# Fostex_CTRL.net
KiCad netlist of a schematic drawn in EAGLE
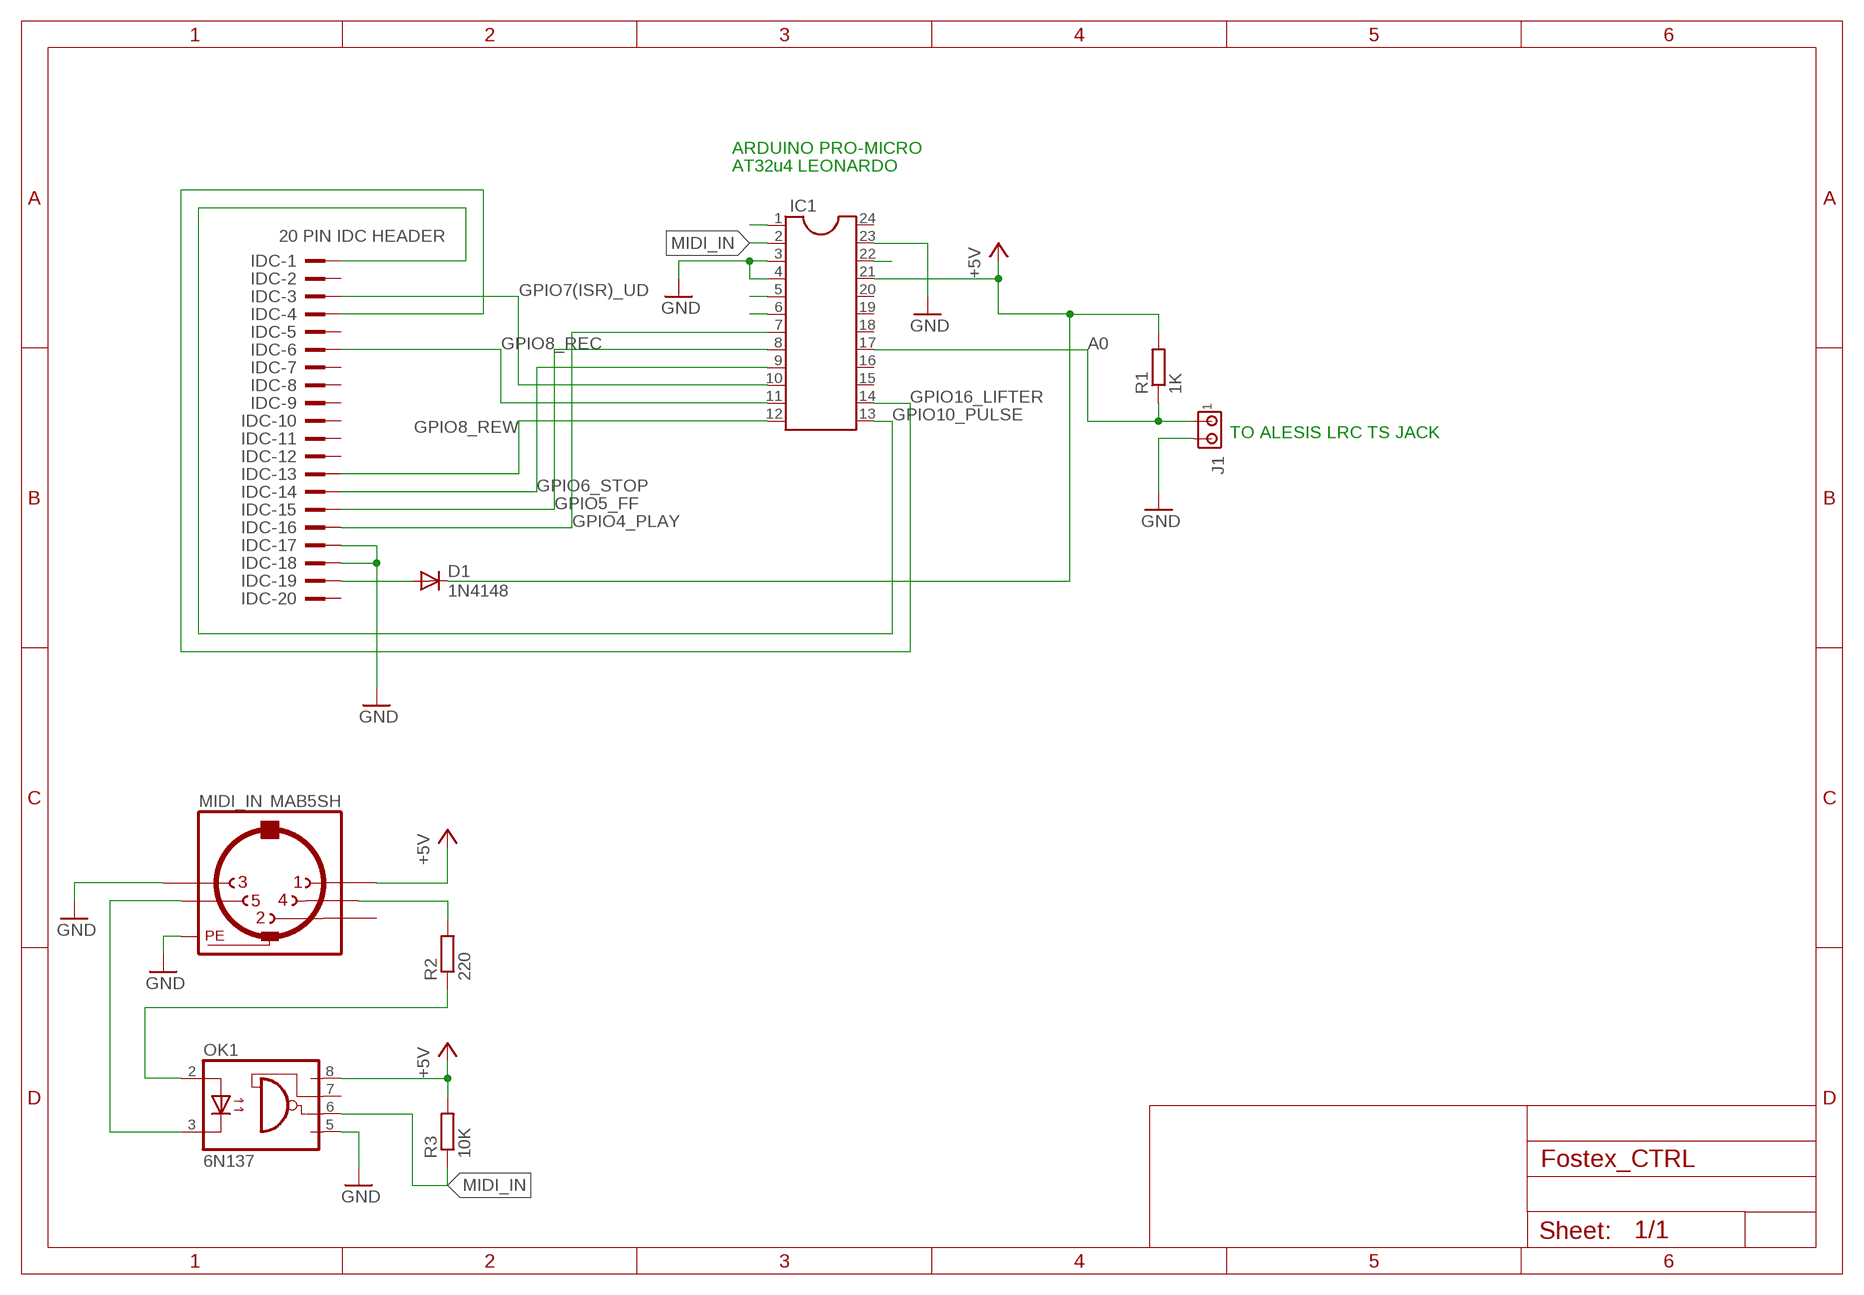
[diagram p0: schematic, sheet 1]

(export (version "E")
  (design (tool "Eeschema 10.0.6"))
  (components
    (comp (ref "D1")
      (value "1N4148")
      (footprint "eagle-import:DO35-7")
      (libsource (lib "eagle-import") (part "1N4148DO35-7"))
    )
    (comp (ref "IC1")
      (value "DIL24-6")
      (footprint "eagle-import:DIL24-6")
      (libsource (lib "eagle-import") (part "DIL24-6"))
    )
    (comp (ref "IDC")
      (value "20 PIN IDC HEADER")
      (footprint "eagle-import:PAK100_2500-20")
      (libsource (lib "eagle-import") (part "2520-"))
    )
    (comp (ref "J1")
      (value "MTA02-100")
      (footprint "eagle-import:10X02MTA")
      (libsource (lib "eagle-import") (part "MTA02-100"))
    )
    (comp (ref "MIDI_IN")
      (value "MAB5SH")
      (footprint "eagle-import:MAB5SH")
      (libsource (lib "eagle-import") (part "MAB5SH"))
    )
    (comp (ref "OK1")
      (value "6N137")
      (footprint "eagle-import:DIL08")
      (libsource (lib "eagle-import") (part "6N137"))
    )
    (comp (ref "R1")
      (value "1K")
      (footprint "eagle-import:0207_7")
      (libsource (lib "eagle-import") (part "R-EU_0207/7"))
    )
    (comp (ref "R2")
      (value "220")
      (footprint "eagle-import:0207_7")
      (libsource (lib "eagle-import") (part "R-EU_0207/7"))
    )
    (comp (ref "R3")
      (value "10K")
      (footprint "eagle-import:0207_7")
      (libsource (lib "eagle-import") (part "R-EU_0207/7"))
    )
  )
  (nets
    (net (code "1") (name "+5V") (class "Default")
      (node (ref "D1") (pin "C") (pinfunction "C_C") (pintype "passive"))
      (node (ref "IC1") (pin "21") (pinfunction "21_21") (pintype "passive"))
      (node (ref "MIDI_IN") (pin "1") (pinfunction "1_1") (pintype "passive"))
      (node (ref "OK1") (pin "8") (pinfunction "VCC_8") (pintype "passive"))
      (node (ref "R1") (pin "2") (pinfunction "2_2") (pintype "passive"))
      (node (ref "R3") (pin "2") (pinfunction "2_2") (pintype "passive"))
    )
    (net (code "2") (name "/A0") (class "Default")
      (node (ref "IC1") (pin "17") (pinfunction "17_17") (pintype "passive"))
      (node (ref "J1") (pin "1") (pinfunction "1_1") (pintype "passive"))
      (node (ref "R1") (pin "1") (pinfunction "1_1") (pintype "passive"))
    )
    (net (code "3") (name "/GPIO4_PLAY") (class "Default")
      (node (ref "IC1") (pin "7") (pinfunction "7_7") (pintype "passive"))
      (node (ref "IDC") (pin "16") (pinfunction "KL_16") (pintype "passive"))
    )
    (net (code "4") (name "/GPIO5_FF") (class "Default")
      (node (ref "IC1") (pin "8") (pinfunction "8_8") (pintype "passive"))
      (node (ref "IDC") (pin "15") (pinfunction "KL_15") (pintype "passive"))
    )
    (net (code "5") (name "/GPIO6_STOP") (class "Default")
      (node (ref "IC1") (pin "9") (pinfunction "9_9") (pintype "passive"))
      (node (ref "IDC") (pin "14") (pinfunction "KL_14") (pintype "passive"))
    )
    (net (code "6") (name "/GPIO7(ISR)_UD") (class "Default")
      (node (ref "IC1") (pin "10") (pinfunction "10_10") (pintype "passive"))
      (node (ref "IDC") (pin "3") (pinfunction "KL_3") (pintype "passive"))
    )
    (net (code "7") (name "/GPIO8_REC") (class "Default")
      (node (ref "IC1") (pin "11") (pinfunction "11_11") (pintype "passive"))
      (node (ref "IDC") (pin "6") (pinfunction "KL_6") (pintype "passive"))
    )
    (net (code "8") (name "/GPIO8_REW") (class "Default")
      (node (ref "IC1") (pin "12") (pinfunction "12_12") (pintype "passive"))
      (node (ref "IDC") (pin "13") (pinfunction "KL_13") (pintype "passive"))
    )
    (net (code "9") (name "/GPIO10_PULSE") (class "Default")
      (node (ref "IC1") (pin "13") (pinfunction "13_13") (pintype "passive"))
      (node (ref "IDC") (pin "1") (pinfunction "KL_1") (pintype "passive"))
    )
    (net (code "10") (name "/GPIO16_LIFTER") (class "Default")
      (node (ref "IC1") (pin "14") (pinfunction "14_14") (pintype "passive"))
      (node (ref "IDC") (pin "4") (pinfunction "KL_4") (pintype "passive"))
    )
    (net (code "11") (name "GND") (class "Default")
      (node (ref "IC1") (pin "23") (pinfunction "23_23") (pintype "passive"))
      (node (ref "IC1") (pin "3") (pinfunction "3_3") (pintype "passive"))
      (node (ref "IC1") (pin "4") (pinfunction "4_4") (pintype "passive"))
      (node (ref "IDC") (pin "17") (pinfunction "KL_17") (pintype "passive"))
      (node (ref "IDC") (pin "18") (pinfunction "KL_18") (pintype "passive"))
      (node (ref "J1") (pin "2") (pinfunction "2_2") (pintype "passive"))
      (node (ref "MIDI_IN") (pin "3") (pinfunction "3_3") (pintype "passive"))
      (node (ref "MIDI_IN") (pin "PE") (pinfunction "PE_PE") (pintype "power_in"))
      (node (ref "MIDI_IN") (pin "PE@") (pinfunction "PE_PE@") (pintype "power_in"))
      (node (ref "OK1") (pin "5") (pinfunction "GND_5") (pintype "passive"))
    )
    (net (code "12") (name "MIDI_IN") (class "Default")
      (node (ref "IC1") (pin "2") (pinfunction "2_2") (pintype "passive"))
      (node (ref "OK1") (pin "6") (pinfunction "VO_6") (pintype "passive"))
      (node (ref "R3") (pin "1") (pinfunction "1_1") (pintype "passive"))
    )
    (net (code "13") (name "Net-(IDCK-KL)") (class "Default")
      (node (ref "D1") (pin "A") (pinfunction "A_A") (pintype "passive"))
      (node (ref "IDC") (pin "19") (pinfunction "KL_19") (pintype "passive"))
    )
    (net (code "14") (name "Net-(MIDI_IN-Pad4)") (class "Default")
      (node (ref "MIDI_IN") (pin "4") (pinfunction "4_4") (pintype "passive"))
      (node (ref "R2") (pin "2") (pinfunction "2_2") (pintype "passive"))
    )
    (net (code "15") (name "Net-(OK1-A)") (class "Default")
      (node (ref "OK1") (pin "2") (pinfunction "A_2") (pintype "passive"))
      (node (ref "R2") (pin "1") (pinfunction "1_1") (pintype "passive"))
    )
    (net (code "16") (name "Net-(OK1-C)") (class "Default")
      (node (ref "MIDI_IN") (pin "5") (pinfunction "5_5") (pintype "passive"))
      (node (ref "OK1") (pin "3") (pinfunction "C_3") (pintype "passive"))
    )
    (net (code "17") (name "unconnected-(IC1-Pad1)") (class "Default")
      (node (ref "IC1") (pin "1") (pinfunction "1_1") (pintype "passive"))
    )
    (net (code "18") (name "unconnected-(IC1-Pad5)") (class "Default")
      (node (ref "IC1") (pin "5") (pinfunction "5_5") (pintype "passive"))
    )
    (net (code "19") (name "unconnected-(IC1-Pad6)") (class "Default")
      (node (ref "IC1") (pin "6") (pinfunction "6_6") (pintype "passive"))
    )
    (net (code "20") (name "unconnected-(IC1-Pad15)") (class "Default")
      (node (ref "IC1") (pin "15") (pinfunction "15_15") (pintype "passive"))
    )
    (net (code "21") (name "unconnected-(IC1-Pad16)") (class "Default")
      (node (ref "IC1") (pin "16") (pinfunction "16_16") (pintype "passive"))
    )
    (net (code "22") (name "unconnected-(IC1-Pad18)") (class "Default")
      (node (ref "IC1") (pin "18") (pinfunction "18_18") (pintype "passive"))
    )
    (net (code "23") (name "unconnected-(IC1-Pad19)") (class "Default")
      (node (ref "IC1") (pin "19") (pinfunction "19_19") (pintype "passive"))
    )
    (net (code "24") (name "unconnected-(IC1-Pad20)") (class "Default")
      (node (ref "IC1") (pin "20") (pinfunction "20_20") (pintype "passive"))
    )
    (net (code "25") (name "unconnected-(IC1-Pad22)") (class "Default")
      (node (ref "IC1") (pin "22") (pinfunction "22_22") (pintype "passive"))
    )
    (net (code "26") (name "unconnected-(IC1-Pad24)") (class "Default")
      (node (ref "IC1") (pin "24") (pinfunction "24_24") (pintype "passive"))
    )
    (net (code "27") (name "unconnected-(IDCB-KL-Pad10)") (class "Default")
      (node (ref "IDC") (pin "10") (pinfunction "KL_10") (pintype "passive"))
    )
    (net (code "28") (name "unconnected-(IDCC-KL-Pad11)") (class "Default")
      (node (ref "IDC") (pin "11") (pinfunction "KL_11") (pintype "passive"))
    )
    (net (code "29") (name "unconnected-(IDCD-KL-Pad12)") (class "Default")
      (node (ref "IDC") (pin "12") (pinfunction "KL_12") (pintype "passive"))
    )
    (net (code "30") (name "unconnected-(IDCL-KL-Pad2)") (class "Default")
      (node (ref "IDC") (pin "2") (pinfunction "KL_2") (pintype "passive"))
    )
    (net (code "31") (name "unconnected-(IDCM-KL-Pad20)") (class "Default")
      (node (ref "IDC") (pin "20") (pinfunction "KL_20") (pintype "passive"))
    )
    (net (code "32") (name "unconnected-(IDCP-KL-Pad5)") (class "Default")
      (node (ref "IDC") (pin "5") (pinfunction "KL_5") (pintype "passive"))
    )
    (net (code "33") (name "unconnected-(IDCR-KL-Pad7)") (class "Default")
      (node (ref "IDC") (pin "7") (pinfunction "KL_7") (pintype "passive"))
    )
    (net (code "34") (name "unconnected-(IDCS-KL-Pad8)") (class "Default")
      (node (ref "IDC") (pin "8") (pinfunction "KL_8") (pintype "passive"))
    )
    (net (code "35") (name "unconnected-(IDCT-KL-Pad9)") (class "Default")
      (node (ref "IDC") (pin "9") (pinfunction "KL_9") (pintype "passive"))
    )
    (net (code "36") (name "unconnected-(MIDI_IN-Pad2)") (class "Default")
      (node (ref "MIDI_IN") (pin "2") (pinfunction "2_2") (pintype "passive"))
    )
    (net (code "37") (name "unconnected-(OK1-VE-Pad7)") (class "Default")
      (node (ref "OK1") (pin "7") (pinfunction "VE_7") (pintype "passive"))
    )
  )
)
